# LED_BUFFER_v1.net
KiCad netlist of a schematic drawn in Altium Designer
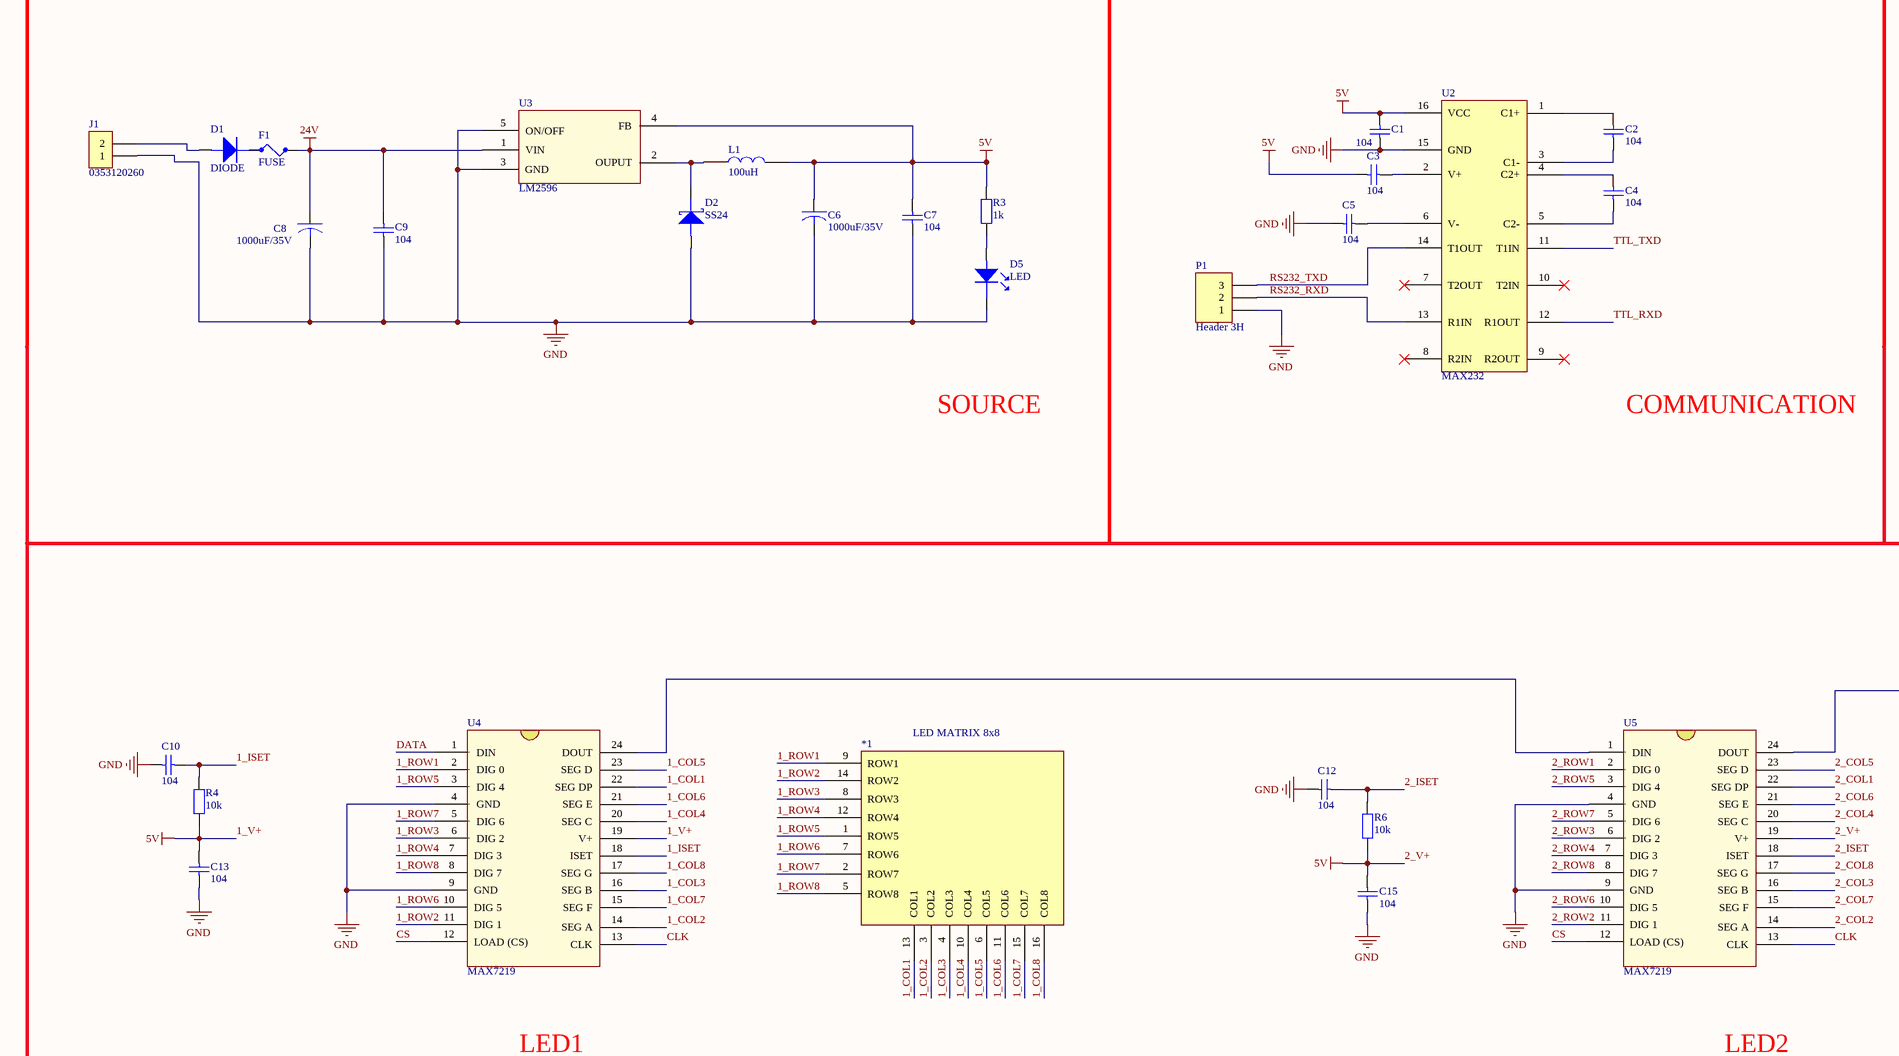
[diagram p0: LED_BUFFER_v1.SchDoc, top left]
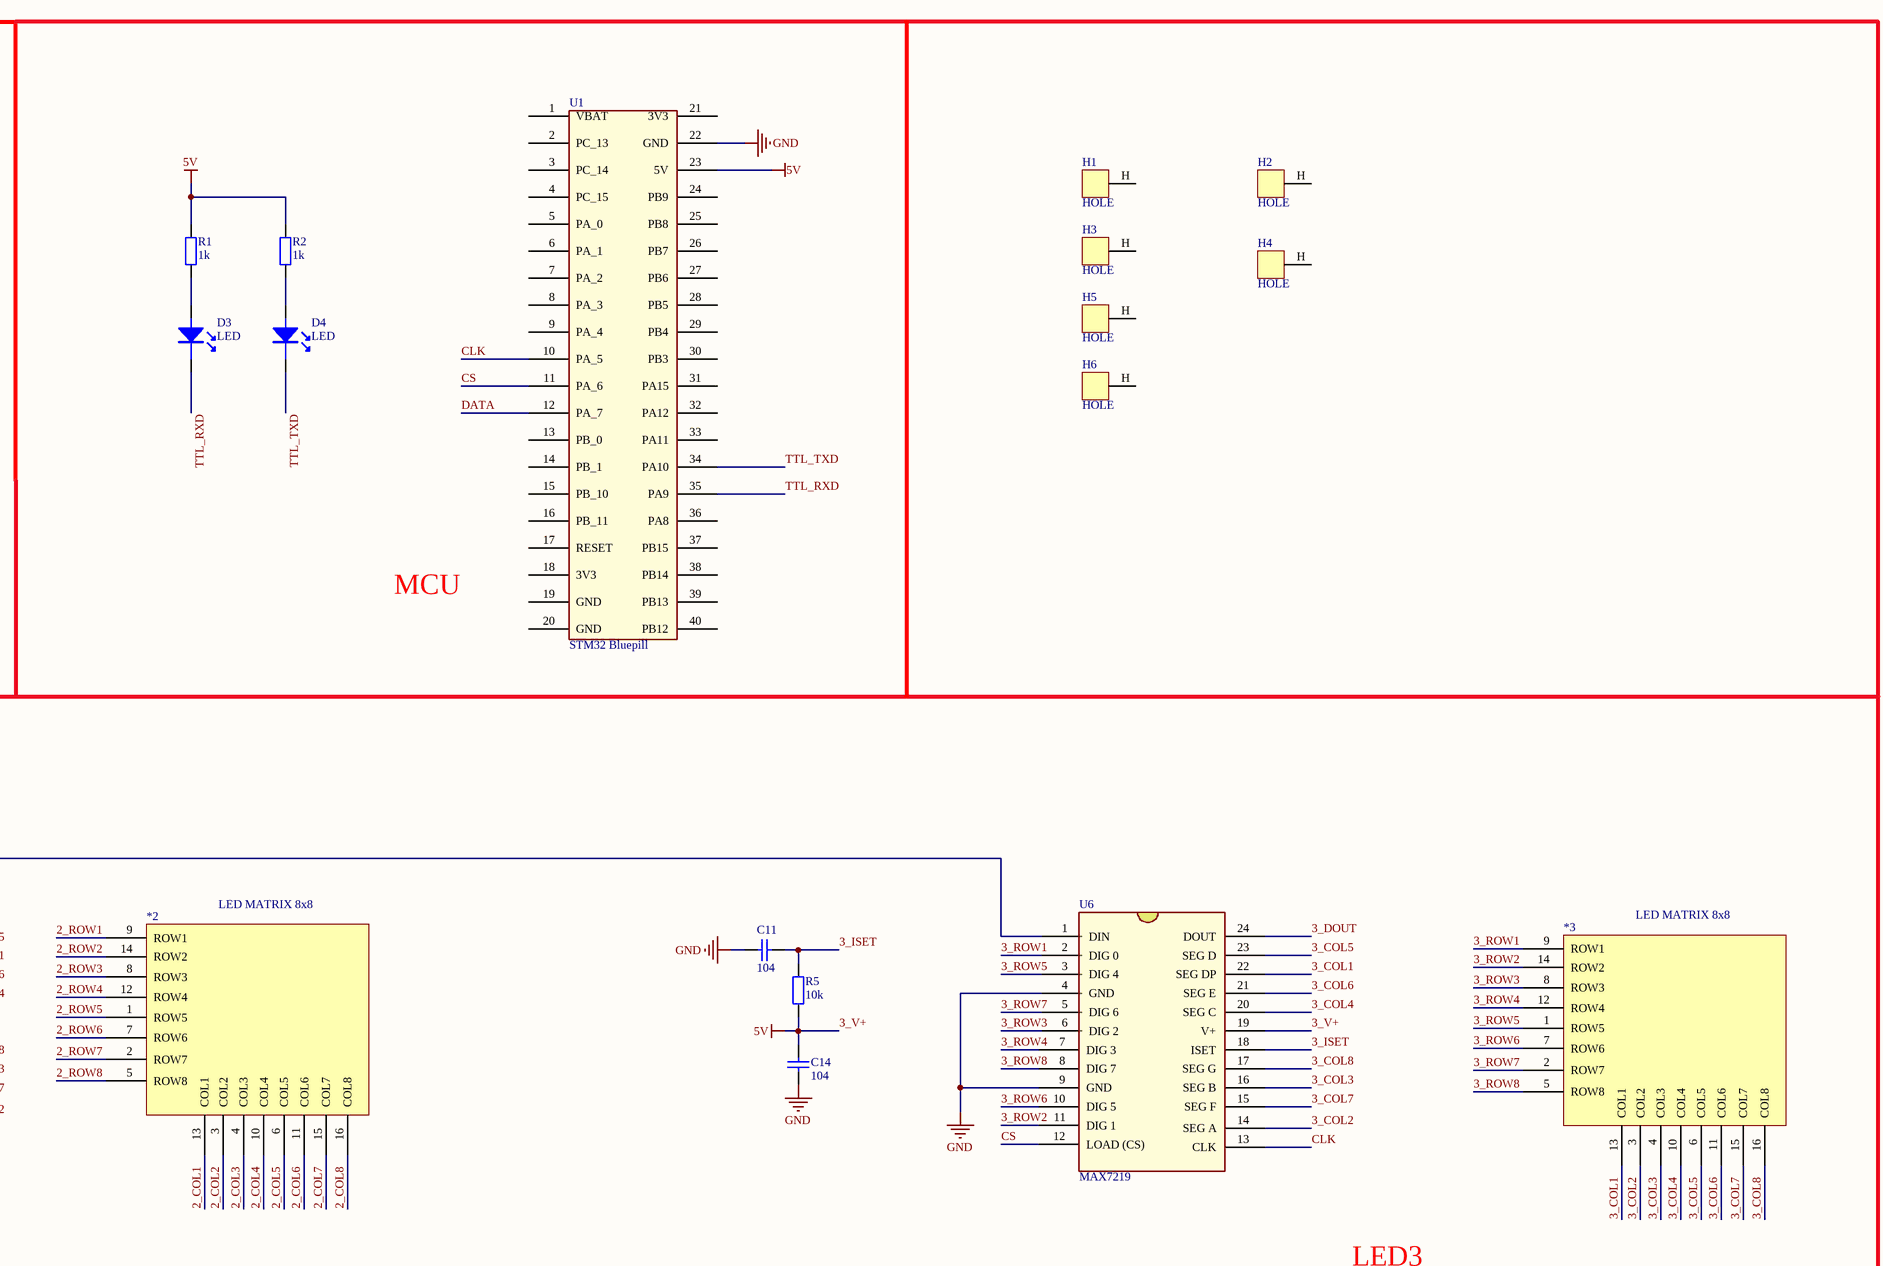
[diagram p1: LED_BUFFER_v1.SchDoc, top right]
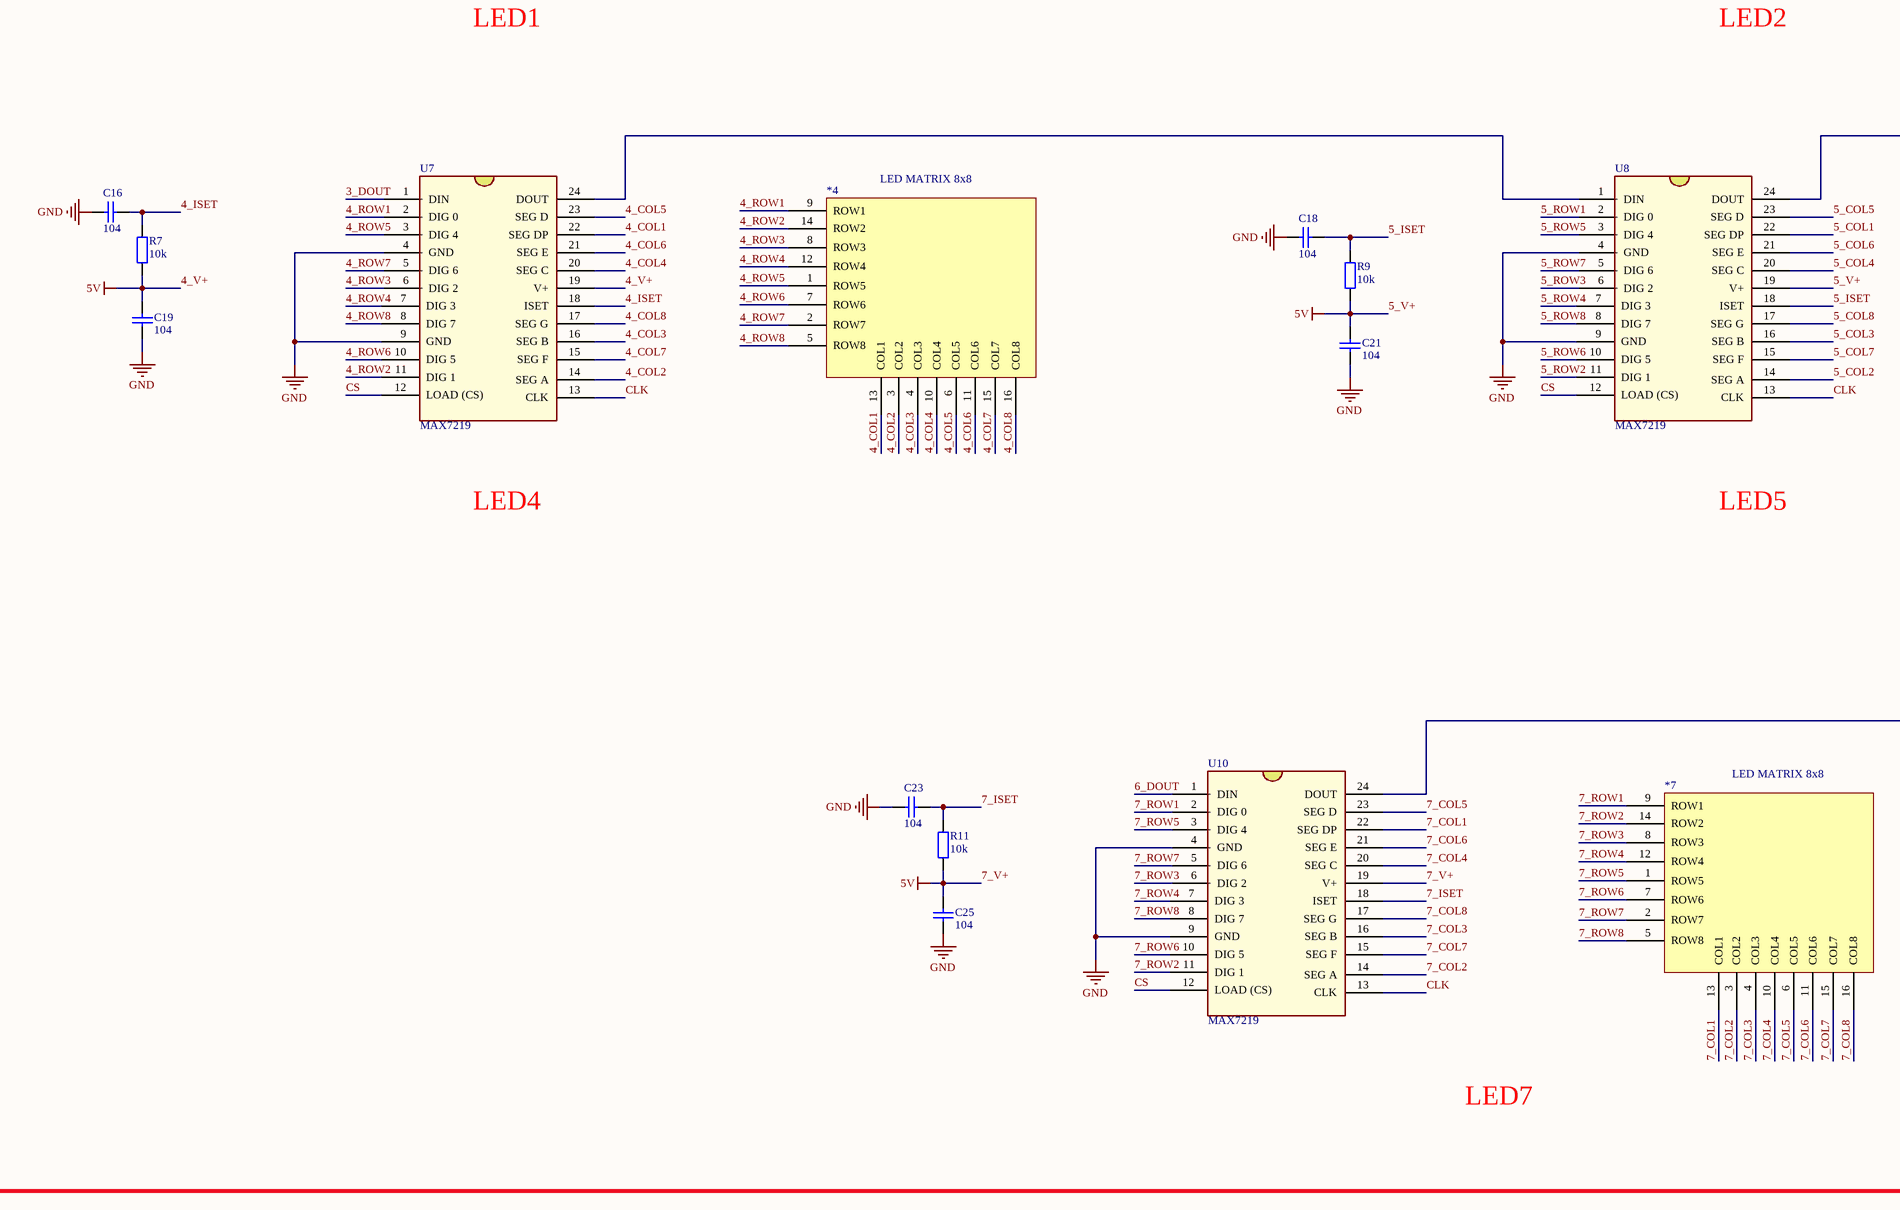
[diagram p2: LED_BUFFER_v1.SchDoc, bottom left]
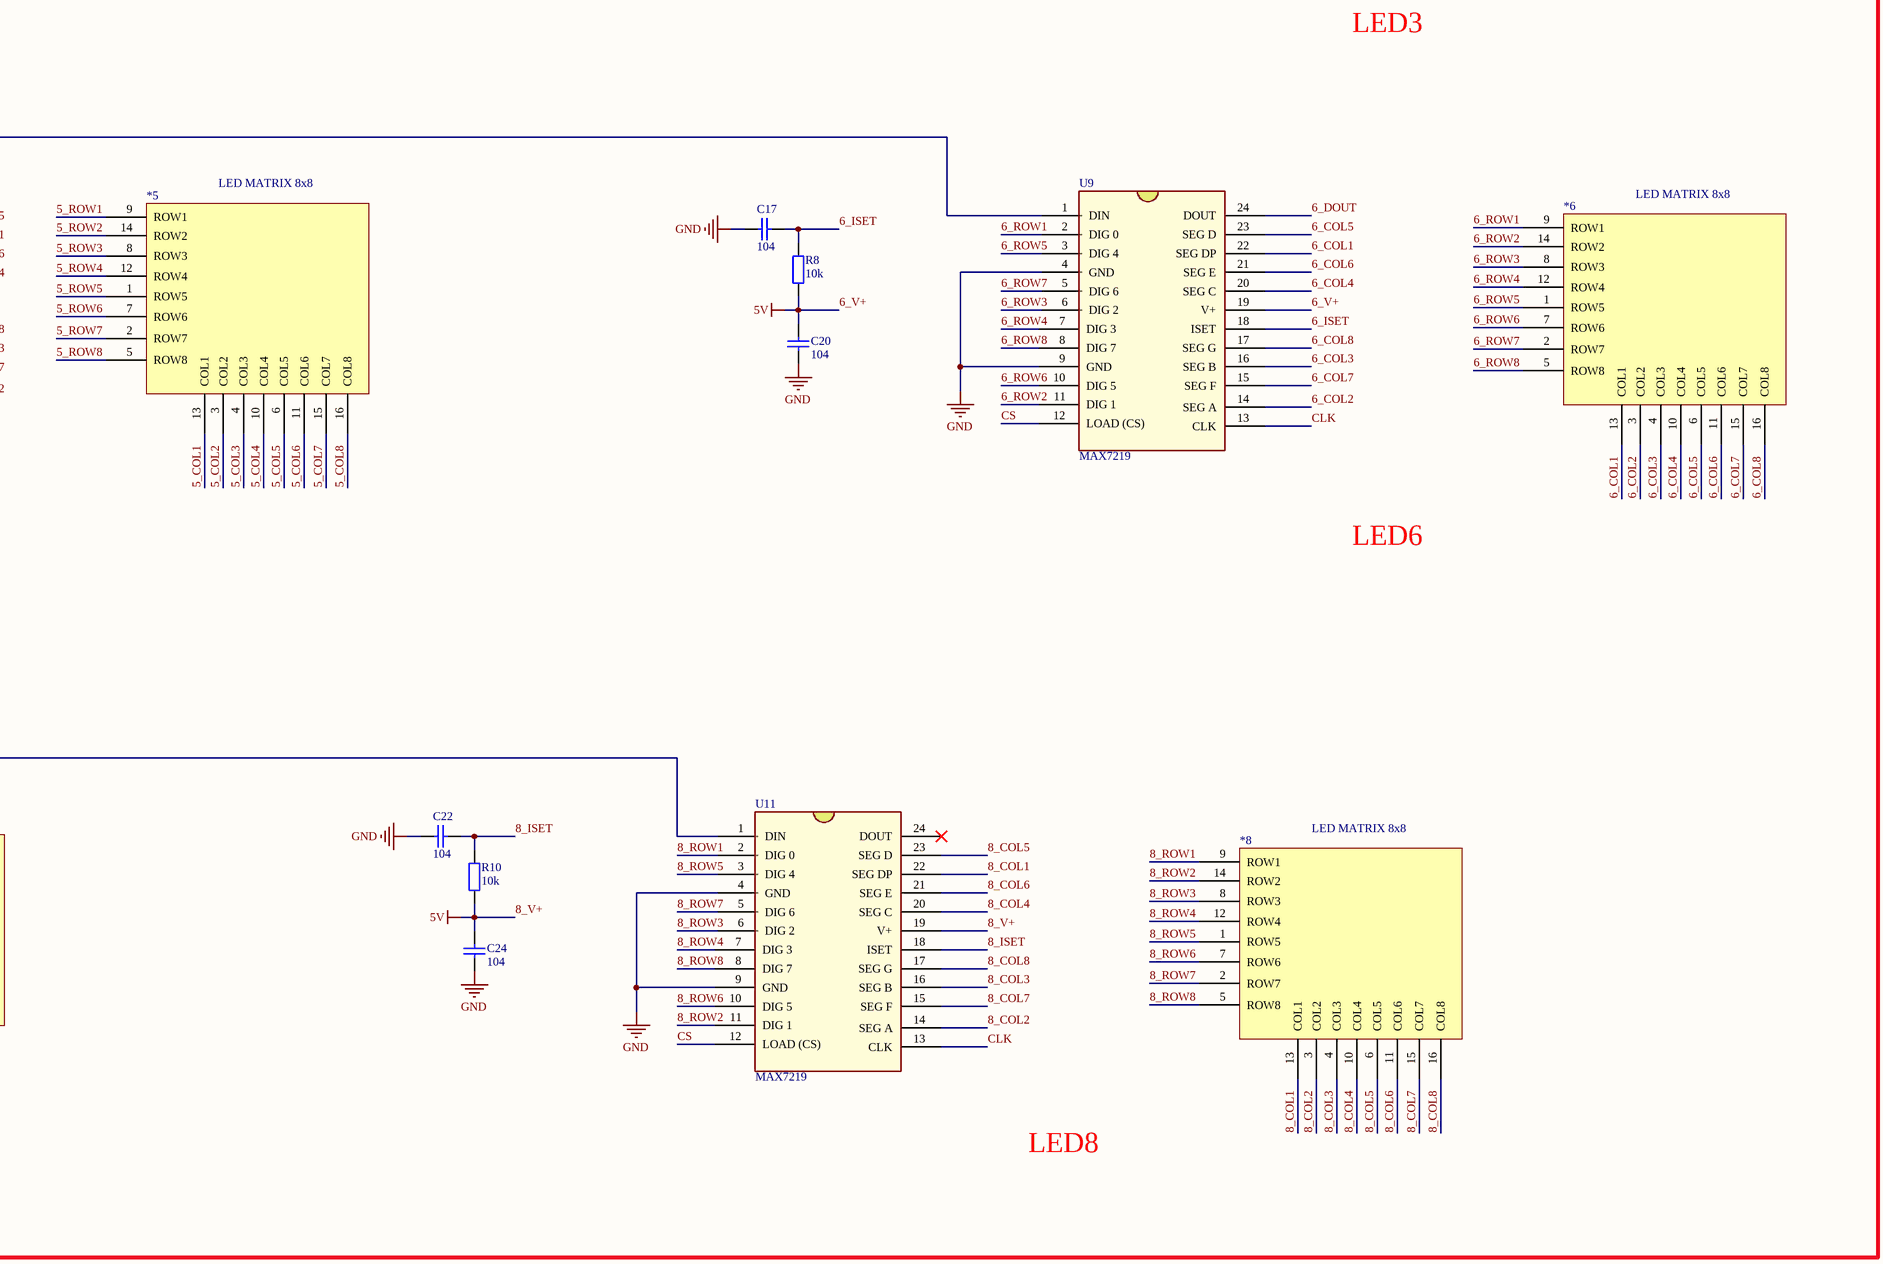
[diagram p3: LED_BUFFER_v1.SchDoc, bottom right]

(export (version "E")
  (design (tool "Eeschema 10.0.6"))
  (components
    (comp (ref "*1")
      (value "LED MATRIX 8x8")
      (footprint "LED MATRIX 8x8")
      (libsource (lib "VietHuy") (part "LED MATRIX 8x8"))
    )
    (comp (ref "*2")
      (value "LED MATRIX 8x8")
      (footprint "LED MATRIX 8x8")
      (libsource (lib "VietHuy") (part "LED MATRIX 8x8"))
    )
    (comp (ref "*3")
      (value "LED MATRIX 8x8")
      (footprint "LED MATRIX 8x8")
      (libsource (lib "VietHuy") (part "LED MATRIX 8x8"))
    )
    (comp (ref "*4")
      (value "LED MATRIX 8x8")
      (footprint "LED MATRIX 8x8")
      (libsource (lib "VietHuy") (part "LED MATRIX 8x8"))
    )
    (comp (ref "*5")
      (value "LED MATRIX 8x8")
      (footprint "LED MATRIX 8x8")
      (libsource (lib "VietHuy") (part "LED MATRIX 8x8"))
    )
    (comp (ref "*6")
      (value "LED MATRIX 8x8")
      (footprint "LED MATRIX 8x8")
      (libsource (lib "VietHuy") (part "LED MATRIX 8x8"))
    )
    (comp (ref "*7")
      (value "LED MATRIX 8x8")
      (footprint "LED MATRIX 8x8")
      (libsource (lib "VietHuy") (part "LED MATRIX 8x8"))
    )
    (comp (ref "*8")
      (value "LED MATRIX 8x8")
      (footprint "LED MATRIX 8x8")
      (libsource (lib "VietHuy") (part "LED MATRIX 8x8"))
    )
    (comp (ref "C1")
      (value "104")
      (footprint "0805 CAP")
      (fields (field (name "PUBLISHER") "Altium Limited"))
      (libsource (lib "ThinhNguyenLib") (part "CAP CERAMIC"))
    )
    (comp (ref "C2")
      (value "104")
      (footprint "0805 CAP")
      (fields (field (name "PUBLISHER") "Altium Limited"))
      (libsource (lib "ThinhNguyenLib") (part "CAP CERAMIC"))
    )
    (comp (ref "C3")
      (value "104")
      (footprint "0805 CAP")
      (fields (field (name "PUBLISHER") "Altium Limited"))
      (libsource (lib "ThinhNguyenLib") (part "CAP CERAMIC"))
    )
    (comp (ref "C4")
      (value "104")
      (footprint "0805 CAP")
      (fields (field (name "PUBLISHER") "Altium Limited"))
      (libsource (lib "ThinhNguyenLib") (part "CAP CERAMIC"))
    )
    (comp (ref "C5")
      (value "104")
      (footprint "0805 CAP")
      (fields (field (name "PUBLISHER") "Altium Limited"))
      (libsource (lib "ThinhNguyenLib") (part "CAP CERAMIC"))
    )
    (comp (ref "C6")
      (value "1000uF/35V")
      (footprint "CAP ALUMINUM SMD")
      (libsource (lib "ThinhNguyenLib") (part "CAPACITOR"))
    )
    (comp (ref "C7")
      (value "104")
      (footprint "0805 CAP")
      (fields (field (name "PUBLISHER") "Altium Limited"))
      (libsource (lib "ThinhNguyenLib") (part "CAP CERAMIC"))
    )
    (comp (ref "C8")
      (value "1000uF/35V")
      (footprint "CAP ALUMINUM SMD")
      (libsource (lib "ThinhNguyenLib") (part "CAPACITOR"))
    )
    (comp (ref "C9")
      (value "104")
      (footprint "0805 CAP")
      (fields (field (name "PUBLISHER") "Altium Limited"))
      (libsource (lib "ThinhNguyenLib") (part "CAP CERAMIC"))
    )
    (comp (ref "C10")
      (value "104")
      (footprint "0805 CAP")
      (fields (field (name "PUBLISHER") "Altium Limited"))
      (libsource (lib "ThinhNguyenLib") (part "CAP CERAMIC"))
    )
    (comp (ref "C11")
      (value "104")
      (footprint "0805 CAP")
      (fields (field (name "PUBLISHER") "Altium Limited"))
      (libsource (lib "ThinhNguyenLib") (part "CAP CERAMIC"))
    )
    (comp (ref "C12")
      (value "104")
      (footprint "0805 CAP")
      (fields (field (name "PUBLISHER") "Altium Limited"))
      (libsource (lib "ThinhNguyenLib") (part "CAP CERAMIC"))
    )
    (comp (ref "C13")
      (value "104")
      (footprint "0805 CAP")
      (fields (field (name "PUBLISHER") "Altium Limited"))
      (libsource (lib "ThinhNguyenLib") (part "CAP CERAMIC"))
    )
    (comp (ref "C14")
      (value "104")
      (footprint "0805 CAP")
      (fields (field (name "PUBLISHER") "Altium Limited"))
      (libsource (lib "ThinhNguyenLib") (part "CAP CERAMIC"))
    )
    (comp (ref "C15")
      (value "104")
      (footprint "0805 CAP")
      (fields (field (name "PUBLISHER") "Altium Limited"))
      (libsource (lib "ThinhNguyenLib") (part "CAP CERAMIC"))
    )
    (comp (ref "C16")
      (value "104")
      (footprint "0805 CAP")
      (fields (field (name "PUBLISHER") "Altium Limited"))
      (libsource (lib "ThinhNguyenLib") (part "CAP CERAMIC"))
    )
    (comp (ref "C17")
      (value "104")
      (footprint "0805 CAP")
      (fields (field (name "PUBLISHER") "Altium Limited"))
      (libsource (lib "ThinhNguyenLib") (part "CAP CERAMIC"))
    )
    (comp (ref "C18")
      (value "104")
      (footprint "0805 CAP")
      (fields (field (name "PUBLISHER") "Altium Limited"))
      (libsource (lib "ThinhNguyenLib") (part "CAP CERAMIC"))
    )
    (comp (ref "C19")
      (value "104")
      (footprint "0805 CAP")
      (fields (field (name "PUBLISHER") "Altium Limited"))
      (libsource (lib "ThinhNguyenLib") (part "CAP CERAMIC"))
    )
    (comp (ref "C20")
      (value "104")
      (footprint "0805 CAP")
      (fields (field (name "PUBLISHER") "Altium Limited"))
      (libsource (lib "ThinhNguyenLib") (part "CAP CERAMIC"))
    )
    (comp (ref "C21")
      (value "104")
      (footprint "0805 CAP")
      (fields (field (name "PUBLISHER") "Altium Limited"))
      (libsource (lib "ThinhNguyenLib") (part "CAP CERAMIC"))
    )
    (comp (ref "C22")
      (value "104")
      (footprint "0805 CAP")
      (fields (field (name "PUBLISHER") "Altium Limited"))
      (libsource (lib "ThinhNguyenLib") (part "CAP CERAMIC"))
    )
    (comp (ref "C23")
      (value "104")
      (footprint "0805 CAP")
      (fields (field (name "PUBLISHER") "Altium Limited"))
      (libsource (lib "ThinhNguyenLib") (part "CAP CERAMIC"))
    )
    (comp (ref "C24")
      (value "104")
      (footprint "0805 CAP")
      (fields (field (name "PUBLISHER") "Altium Limited"))
      (libsource (lib "ThinhNguyenLib") (part "CAP CERAMIC"))
    )
    (comp (ref "C25")
      (value "104")
      (footprint "0805 CAP")
      (fields (field (name "PUBLISHER") "Altium Limited"))
      (libsource (lib "ThinhNguyenLib") (part "CAP CERAMIC"))
    )
    (comp (ref "D1")
      (value "DIODE")
      (footprint "DIODE SMA")
      (libsource (lib "ThinhNguyenLib") (part "DIODE"))
    )
    (comp (ref "D2")
      (value "SS24")
      (footprint "DIODE ZENER SMD")
      (libsource (lib "ThinhNguyenLib") (part "SS1x"))
    )
    (comp (ref "D3") (value "LED") (footprint "LED SMD 0805") (libsource (lib "ThinhNguyenLib") (part "LED")))
    (comp (ref "D4") (value "LED") (footprint "LED SMD 0805") (libsource (lib "ThinhNguyenLib") (part "LED")))
    (comp (ref "D5") (value "LED") (footprint "LED SMD 0805") (libsource (lib "ThinhNguyenLib") (part "LED")))
    (comp (ref "F1")
      (value "FUSE")
      (footprint "FUSE 1812")
      (fields (field (name "ALTIUM_UNNAMED_1") "FUSE"))
      (libsource (lib "HHP_AGV_INTERFACES") (part "FUSE"))
    )
    (comp (ref "H1") (value "HOLE") (footprint "HOLE") (libsource (lib "ThinhNguyenLib") (part "HOLE")))
    (comp (ref "H2") (value "HOLE") (footprint "HOLE") (libsource (lib "ThinhNguyenLib") (part "HOLE")))
    (comp (ref "H3") (value "HOLE") (footprint "HOLE") (libsource (lib "ThinhNguyenLib") (part "HOLE")))
    (comp (ref "H4") (value "HOLE") (footprint "HOLE") (libsource (lib "ThinhNguyenLib") (part "HOLE")))
    (comp (ref "H5") (value "HOLE") (footprint "HOLE") (libsource (lib "ThinhNguyenLib") (part "HOLE")))
    (comp (ref "H6") (value "HOLE") (footprint "HOLE") (libsource (lib "ThinhNguyenLib") (part "HOLE")))
    (comp (ref "J1")
      (value "CONN HEADER VERT 2POS 2.5MM")
      (footprint "0353120260")
      (fields (field (name "P/N") "0353120260"))
      (libsource (lib "altium-import") (part "root_2_CONN HEADER VERT 2POS 2.5MM_"))
    )
    (comp (ref "L1")
      (value "100uH")
      (footprint "CDRH127 - 3A")
      (libsource (lib "ThinhNguyenLib") (part "INDUCTOR"))
    )
    (comp (ref "P1")
      (value "Header 3H")
      (footprint "HDR1X3 2mm")
      (fields (field (name "PUBLISHER") "Altium Limited"))
      (libsource (lib "ThinhNguyenLib") (part "Header 3H"))
    )
    (comp (ref "R1")
      (value "1k")
      (footprint "0805 RESISTOR")
      (libsource (lib "ThinhNguyenLib") (part "RESISTOR"))
    )
    (comp (ref "R2")
      (value "1k")
      (footprint "0805 RESISTOR")
      (libsource (lib "ThinhNguyenLib") (part "RESISTOR"))
    )
    (comp (ref "R3")
      (value "1k")
      (footprint "0805 RESISTOR")
      (libsource (lib "ThinhNguyenLib") (part "RESISTOR"))
    )
    (comp (ref "R4")
      (value "10k")
      (footprint "0805 RESISTOR")
      (libsource (lib "ThinhNguyenLib") (part "RESISTOR"))
    )
    (comp (ref "R5")
      (value "10k")
      (footprint "0805 RESISTOR")
      (libsource (lib "ThinhNguyenLib") (part "RESISTOR"))
    )
    (comp (ref "R6")
      (value "10k")
      (footprint "0805 RESISTOR")
      (libsource (lib "ThinhNguyenLib") (part "RESISTOR"))
    )
    (comp (ref "R7")
      (value "10k")
      (footprint "0805 RESISTOR")
      (libsource (lib "ThinhNguyenLib") (part "RESISTOR"))
    )
    (comp (ref "R8")
      (value "10k")
      (footprint "0805 RESISTOR")
      (libsource (lib "ThinhNguyenLib") (part "RESISTOR"))
    )
    (comp (ref "R9")
      (value "10k")
      (footprint "0805 RESISTOR")
      (libsource (lib "ThinhNguyenLib") (part "RESISTOR"))
    )
    (comp (ref "R10")
      (value "10k")
      (footprint "0805 RESISTOR")
      (libsource (lib "ThinhNguyenLib") (part "RESISTOR"))
    )
    (comp (ref "R11")
      (value "10k")
      (footprint "0805 RESISTOR")
      (libsource (lib "ThinhNguyenLib") (part "RESISTOR"))
    )
    (comp (ref "U1")
      (value "STM32 Bluepill")
      (footprint "Arduino STM32F103")
      (libsource (lib "VietHuy") (part "STM32 Bluepill"))
    )
    (comp (ref "U2") (value "MAX232") (footprint "SOIC 16PIN") (libsource (lib "VietHuy") (part "MAX232")))
    (comp (ref "U3") (value "LM2596") (footprint "TO263-5") (libsource (lib "VietHuy") (part "LM2596")))
    (comp (ref "U4")
      (value "MAX7219")
      (footprint "SOIC127P1030X265-24N")
      (libsource (lib "VietHuy") (part "MAX7219"))
    )
    (comp (ref "U5")
      (value "MAX7219")
      (footprint "SOIC127P1030X265-24N")
      (libsource (lib "VietHuy") (part "MAX7219"))
    )
    (comp (ref "U6")
      (value "MAX7219")
      (footprint "SOIC127P1030X265-24N")
      (libsource (lib "VietHuy") (part "MAX7219"))
    )
    (comp (ref "U7")
      (value "MAX7219")
      (footprint "SOIC127P1030X265-24N")
      (libsource (lib "VietHuy") (part "MAX7219"))
    )
    (comp (ref "U8")
      (value "MAX7219")
      (footprint "SOIC127P1030X265-24N")
      (libsource (lib "VietHuy") (part "MAX7219"))
    )
    (comp (ref "U9")
      (value "MAX7219")
      (footprint "SOIC127P1030X265-24N")
      (libsource (lib "VietHuy") (part "MAX7219"))
    )
    (comp (ref "U10")
      (value "MAX7219")
      (footprint "SOIC127P1030X265-24N")
      (libsource (lib "VietHuy") (part "MAX7219"))
    )
    (comp (ref "U11")
      (value "MAX7219")
      (footprint "SOIC127P1030X265-24N")
      (libsource (lib "VietHuy") (part "MAX7219"))
    )
  )
  (nets
    (net (code "1") (name "/1_COL1") (class "Default")
      (node (ref "*1") (pin "13") (pinfunction "COL1_13") (pintype "passive"))
      (node (ref "U4") (pin "22") (pinfunction "SEG_DP_22") (pintype "passive"))
    )
    (net (code "2") (name "/1_COL2") (class "Default")
      (node (ref "*1") (pin "3") (pinfunction "COL2_3") (pintype "passive"))
      (node (ref "U4") (pin "14") (pinfunction "SEG_A_14") (pintype "passive"))
    )
    (net (code "3") (name "/1_COL3") (class "Default")
      (node (ref "*1") (pin "4") (pinfunction "COL3_4") (pintype "passive"))
      (node (ref "U4") (pin "16") (pinfunction "SEG_B_16") (pintype "passive"))
    )
    (net (code "4") (name "/1_COL4") (class "Default")
      (node (ref "*1") (pin "10") (pinfunction "COL4_10") (pintype "passive"))
      (node (ref "U4") (pin "20") (pinfunction "SEG_C_20") (pintype "passive"))
    )
    (net (code "5") (name "/1_COL5") (class "Default")
      (node (ref "*1") (pin "6") (pinfunction "COL5_6") (pintype "passive"))
      (node (ref "U4") (pin "23") (pinfunction "SEG_D_23") (pintype "passive"))
    )
    (net (code "6") (name "/1_COL6") (class "Default")
      (node (ref "*1") (pin "11") (pinfunction "COL6_11") (pintype "passive"))
      (node (ref "U4") (pin "21") (pinfunction "SEG_E_21") (pintype "passive"))
    )
    (net (code "7") (name "/1_COL7") (class "Default")
      (node (ref "*1") (pin "15") (pinfunction "COL7_15") (pintype "passive"))
      (node (ref "U4") (pin "15") (pinfunction "SEG_F_15") (pintype "passive"))
    )
    (net (code "8") (name "/1_COL8") (class "Default")
      (node (ref "*1") (pin "16") (pinfunction "COL8_16") (pintype "passive"))
      (node (ref "U4") (pin "17") (pinfunction "SEG_G_17") (pintype "passive"))
    )
    (net (code "9") (name "/1_ISET") (class "Default")
      (node (ref "C10") (pin "2") (pinfunction "2_2") (pintype "passive"))
      (node (ref "R4") (pin "2") (pinfunction "2_2") (pintype "passive"))
      (node (ref "U4") (pin "18") (pinfunction "ISET_18") (pintype "passive"))
    )
    (net (code "10") (name "/1_ROW1") (class "Default")
      (node (ref "*1") (pin "9") (pinfunction "ROW1_9") (pintype "passive"))
      (node (ref "U4") (pin "2") (pinfunction "DIG_0_2") (pintype "passive"))
    )
    (net (code "11") (name "/1_ROW2") (class "Default")
      (node (ref "*1") (pin "14") (pinfunction "ROW2_14") (pintype "passive"))
      (node (ref "U4") (pin "11") (pinfunction "DIG_1_11") (pintype "passive"))
    )
    (net (code "12") (name "/1_ROW3") (class "Default")
      (node (ref "*1") (pin "8") (pinfunction "ROW3_8") (pintype "passive"))
      (node (ref "U4") (pin "6") (pinfunction "DIG_2_6") (pintype "passive"))
    )
    (net (code "13") (name "/1_ROW4") (class "Default")
      (node (ref "*1") (pin "12") (pinfunction "ROW4_12") (pintype "passive"))
      (node (ref "U4") (pin "7") (pinfunction "DIG_3_7") (pintype "passive"))
    )
    (net (code "14") (name "/1_ROW5") (class "Default")
      (node (ref "*1") (pin "1") (pinfunction "ROW5_1") (pintype "passive"))
      (node (ref "U4") (pin "3") (pinfunction "DIG_4_3") (pintype "passive"))
    )
    (net (code "15") (name "/1_ROW6") (class "Default")
      (node (ref "*1") (pin "7") (pinfunction "ROW6_7") (pintype "passive"))
      (node (ref "U4") (pin "10") (pinfunction "DIG_5_10") (pintype "passive"))
    )
    (net (code "16") (name "/1_ROW7") (class "Default")
      (node (ref "*1") (pin "2") (pinfunction "ROW7_2") (pintype "passive"))
      (node (ref "U4") (pin "5") (pinfunction "DIG_6_5") (pintype "passive"))
    )
    (net (code "17") (name "/1_ROW8") (class "Default")
      (node (ref "*1") (pin "5") (pinfunction "ROW8_5") (pintype "passive"))
      (node (ref "U4") (pin "8") (pinfunction "DIG_7_8") (pintype "passive"))
    )
    (net (code "18") (name "/2_COL1") (class "Default")
      (node (ref "*2") (pin "13") (pinfunction "COL1_13") (pintype "passive"))
      (node (ref "U5") (pin "22") (pinfunction "SEG_DP_22") (pintype "passive"))
    )
    (net (code "19") (name "/2_COL2") (class "Default")
      (node (ref "*2") (pin "3") (pinfunction "COL2_3") (pintype "passive"))
      (node (ref "U5") (pin "14") (pinfunction "SEG_A_14") (pintype "passive"))
    )
    (net (code "20") (name "/2_COL3") (class "Default")
      (node (ref "*2") (pin "4") (pinfunction "COL3_4") (pintype "passive"))
      (node (ref "U5") (pin "16") (pinfunction "SEG_B_16") (pintype "passive"))
    )
    (net (code "21") (name "/2_COL4") (class "Default")
      (node (ref "*2") (pin "10") (pinfunction "COL4_10") (pintype "passive"))
      (node (ref "U5") (pin "20") (pinfunction "SEG_C_20") (pintype "passive"))
    )
    (net (code "22") (name "/2_COL5") (class "Default")
      (node (ref "*2") (pin "6") (pinfunction "COL5_6") (pintype "passive"))
      (node (ref "U5") (pin "23") (pinfunction "SEG_D_23") (pintype "passive"))
    )
    (net (code "23") (name "/2_COL6") (class "Default")
      (node (ref "*2") (pin "11") (pinfunction "COL6_11") (pintype "passive"))
      (node (ref "U5") (pin "21") (pinfunction "SEG_E_21") (pintype "passive"))
    )
    (net (code "24") (name "/2_COL7") (class "Default")
      (node (ref "*2") (pin "15") (pinfunction "COL7_15") (pintype "passive"))
      (node (ref "U5") (pin "15") (pinfunction "SEG_F_15") (pintype "passive"))
    )
    (net (code "25") (name "/2_COL8") (class "Default")
      (node (ref "*2") (pin "16") (pinfunction "COL8_16") (pintype "passive"))
      (node (ref "U5") (pin "17") (pinfunction "SEG_G_17") (pintype "passive"))
    )
    (net (code "26") (name "/2_ISET") (class "Default")
      (node (ref "C12") (pin "2") (pinfunction "2_2") (pintype "passive"))
      (node (ref "R6") (pin "2") (pinfunction "2_2") (pintype "passive"))
      (node (ref "U5") (pin "18") (pinfunction "ISET_18") (pintype "passive"))
    )
    (net (code "27") (name "/2_ROW1") (class "Default")
      (node (ref "*2") (pin "9") (pinfunction "ROW1_9") (pintype "passive"))
      (node (ref "U5") (pin "2") (pinfunction "DIG_0_2") (pintype "passive"))
    )
    (net (code "28") (name "/2_ROW2") (class "Default")
      (node (ref "*2") (pin "14") (pinfunction "ROW2_14") (pintype "passive"))
      (node (ref "U5") (pin "11") (pinfunction "DIG_1_11") (pintype "passive"))
    )
    (net (code "29") (name "/2_ROW3") (class "Default")
      (node (ref "*2") (pin "8") (pinfunction "ROW3_8") (pintype "passive"))
      (node (ref "U5") (pin "6") (pinfunction "DIG_2_6") (pintype "passive"))
    )
    (net (code "30") (name "/2_ROW4") (class "Default")
      (node (ref "*2") (pin "12") (pinfunction "ROW4_12") (pintype "passive"))
      (node (ref "U5") (pin "7") (pinfunction "DIG_3_7") (pintype "passive"))
    )
    (net (code "31") (name "/2_ROW5") (class "Default")
      (node (ref "*2") (pin "1") (pinfunction "ROW5_1") (pintype "passive"))
      (node (ref "U5") (pin "3") (pinfunction "DIG_4_3") (pintype "passive"))
    )
    (net (code "32") (name "/2_ROW6") (class "Default")
      (node (ref "*2") (pin "7") (pinfunction "ROW6_7") (pintype "passive"))
      (node (ref "U5") (pin "10") (pinfunction "DIG_5_10") (pintype "passive"))
    )
    (net (code "33") (name "/2_ROW7") (class "Default")
      (node (ref "*2") (pin "2") (pinfunction "ROW7_2") (pintype "passive"))
      (node (ref "U5") (pin "5") (pinfunction "DIG_6_5") (pintype "passive"))
    )
    (net (code "34") (name "/2_ROW8") (class "Default")
      (node (ref "*2") (pin "5") (pinfunction "ROW8_5") (pintype "passive"))
      (node (ref "U5") (pin "8") (pinfunction "DIG_7_8") (pintype "passive"))
    )
    (net (code "35") (name "/3_COL1") (class "Default")
      (node (ref "*3") (pin "13") (pinfunction "COL1_13") (pintype "passive"))
      (node (ref "U6") (pin "22") (pinfunction "SEG_DP_22") (pintype "passive"))
    )
    (net (code "36") (name "/3_COL2") (class "Default")
      (node (ref "*3") (pin "3") (pinfunction "COL2_3") (pintype "passive"))
      (node (ref "U6") (pin "14") (pinfunction "SEG_A_14") (pintype "passive"))
    )
    (net (code "37") (name "/3_COL3") (class "Default")
      (node (ref "*3") (pin "4") (pinfunction "COL3_4") (pintype "passive"))
      (node (ref "U6") (pin "16") (pinfunction "SEG_B_16") (pintype "passive"))
    )
    (net (code "38") (name "/3_COL4") (class "Default")
      (node (ref "*3") (pin "10") (pinfunction "COL4_10") (pintype "passive"))
      (node (ref "U6") (pin "20") (pinfunction "SEG_C_20") (pintype "passive"))
    )
    (net (code "39") (name "/3_COL5") (class "Default")
      (node (ref "*3") (pin "6") (pinfunction "COL5_6") (pintype "passive"))
      (node (ref "U6") (pin "23") (pinfunction "SEG_D_23") (pintype "passive"))
    )
    (net (code "40") (name "/3_COL6") (class "Default")
      (node (ref "*3") (pin "11") (pinfunction "COL6_11") (pintype "passive"))
      (node (ref "U6") (pin "21") (pinfunction "SEG_E_21") (pintype "passive"))
    )
    (net (code "41") (name "/3_COL7") (class "Default")
      (node (ref "*3") (pin "15") (pinfunction "COL7_15") (pintype "passive"))
      (node (ref "U6") (pin "15") (pinfunction "SEG_F_15") (pintype "passive"))
    )
    (net (code "42") (name "/3_COL8") (class "Default")
      (node (ref "*3") (pin "16") (pinfunction "COL8_16") (pintype "passive"))
      (node (ref "U6") (pin "17") (pinfunction "SEG_G_17") (pintype "passive"))
    )
    (net (code "43") (name "/3_DOUT") (class "Default")
      (node (ref "U6") (pin "24") (pinfunction "DOUT_24") (pintype "passive"))
      (node (ref "U7") (pin "1") (pinfunction "DIN_1") (pintype "passive"))
    )
    (net (code "44") (name "/3_ISET") (class "Default")
      (node (ref "C11") (pin "2") (pinfunction "2_2") (pintype "passive"))
      (node (ref "R5") (pin "2") (pinfunction "2_2") (pintype "passive"))
      (node (ref "U6") (pin "18") (pinfunction "ISET_18") (pintype "passive"))
    )
    (net (code "45") (name "/3_ROW1") (class "Default")
      (node (ref "*3") (pin "9") (pinfunction "ROW1_9") (pintype "passive"))
      (node (ref "U6") (pin "2") (pinfunction "DIG_0_2") (pintype "passive"))
    )
    (net (code "46") (name "/3_ROW2") (class "Default")
      (node (ref "*3") (pin "14") (pinfunction "ROW2_14") (pintype "passive"))
      (node (ref "U6") (pin "11") (pinfunction "DIG_1_11") (pintype "passive"))
    )
    (net (code "47") (name "/3_ROW3") (class "Default")
      (node (ref "*3") (pin "8") (pinfunction "ROW3_8") (pintype "passive"))
      (node (ref "U6") (pin "6") (pinfunction "DIG_2_6") (pintype "passive"))
    )
    (net (code "48") (name "/3_ROW4") (class "Default")
      (node (ref "*3") (pin "12") (pinfunction "ROW4_12") (pintype "passive"))
      (node (ref "U6") (pin "7") (pinfunction "DIG_3_7") (pintype "passive"))
    )
    (net (code "49") (name "/3_ROW5") (class "Default")
      (node (ref "*3") (pin "1") (pinfunction "ROW5_1") (pintype "passive"))
      (node (ref "U6") (pin "3") (pinfunction "DIG_4_3") (pintype "passive"))
    )
    (net (code "50") (name "/3_ROW6") (class "Default")
      (node (ref "*3") (pin "7") (pinfunction "ROW6_7") (pintype "passive"))
      (node (ref "U6") (pin "10") (pinfunction "DIG_5_10") (pintype "passive"))
    )
    (net (code "51") (name "/3_ROW7") (class "Default")
      (node (ref "*3") (pin "2") (pinfunction "ROW7_2") (pintype "passive"))
      (node (ref "U6") (pin "5") (pinfunction "DIG_6_5") (pintype "passive"))
    )
    (net (code "52") (name "/3_ROW8") (class "Default")
      (node (ref "*3") (pin "5") (pinfunction "ROW8_5") (pintype "passive"))
      (node (ref "U6") (pin "8") (pinfunction "DIG_7_8") (pintype "passive"))
    )
    (net (code "53") (name "/4_COL1") (class "Default")
      (node (ref "*4") (pin "13") (pinfunction "COL1_13") (pintype "passive"))
      (node (ref "U7") (pin "22") (pinfunction "SEG_DP_22") (pintype "passive"))
    )
    (net (code "54") (name "/4_COL2") (class "Default")
      (node (ref "*4") (pin "3") (pinfunction "COL2_3") (pintype "passive"))
      (node (ref "U7") (pin "14") (pinfunction "SEG_A_14") (pintype "passive"))
    )
    (net (code "55") (name "/4_COL3") (class "Default")
      (node (ref "*4") (pin "4") (pinfunction "COL3_4") (pintype "passive"))
      (node (ref "U7") (pin "16") (pinfunction "SEG_B_16") (pintype "passive"))
    )
    (net (code "56") (name "/4_COL4") (class "Default")
      (node (ref "*4") (pin "10") (pinfunction "COL4_10") (pintype "passive"))
      (node (ref "U7") (pin "20") (pinfunction "SEG_C_20") (pintype "passive"))
    )
    (net (code "57") (name "/4_COL5") (class "Default")
      (node (ref "*4") (pin "6") (pinfunction "COL5_6") (pintype "passive"))
      (node (ref "U7") (pin "23") (pinfunction "SEG_D_23") (pintype "passive"))
    )
    (net (code "58") (name "/4_COL6") (class "Default")
      (node (ref "*4") (pin "11") (pinfunction "COL6_11") (pintype "passive"))
      (node (ref "U7") (pin "21") (pinfunction "SEG_E_21") (pintype "passive"))
    )
    (net (code "59") (name "/4_COL7") (class "Default")
      (node (ref "*4") (pin "15") (pinfunction "COL7_15") (pintype "passive"))
      (node (ref "U7") (pin "15") (pinfunction "SEG_F_15") (pintype "passive"))
    )
    (net (code "60") (name "/4_COL8") (class "Default")
      (node (ref "*4") (pin "16") (pinfunction "COL8_16") (pintype "passive"))
      (node (ref "U7") (pin "17") (pinfunction "SEG_G_17") (pintype "passive"))
    )
    (net (code "61") (name "/4_ISET") (class "Default")
      (node (ref "C16") (pin "2") (pinfunction "2_2") (pintype "passive"))
      (node (ref "R7") (pin "2") (pinfunction "2_2") (pintype "passive"))
      (node (ref "U7") (pin "18") (pinfunction "ISET_18") (pintype "passive"))
    )
    (net (code "62") (name "/4_ROW1") (class "Default")
      (node (ref "*4") (pin "9") (pinfunction "ROW1_9") (pintype "passive"))
      (node (ref "U7") (pin "2") (pinfunction "DIG_0_2") (pintype "passive"))
    )
    (net (code "63") (name "/4_ROW2") (class "Default")
      (node (ref "*4") (pin "14") (pinfunction "ROW2_14") (pintype "passive"))
      (node (ref "U7") (pin "11") (pinfunction "DIG_1_11") (pintype "passive"))
    )
    (net (code "64") (name "/4_ROW3") (class "Default")
      (node (ref "*4") (pin "8") (pinfunction "ROW3_8") (pintype "passive"))
      (node (ref "U7") (pin "6") (pinfunction "DIG_2_6") (pintype "passive"))
    )
    (net (code "65") (name "/4_ROW4") (class "Default")
      (node (ref "*4") (pin "12") (pinfunction "ROW4_12") (pintype "passive"))
      (node (ref "U7") (pin "7") (pinfunction "DIG_3_7") (pintype "passive"))
    )
    (net (code "66") (name "/4_ROW5") (class "Default")
      (node (ref "*4") (pin "1") (pinfunction "ROW5_1") (pintype "passive"))
      (node (ref "U7") (pin "3") (pinfunction "DIG_4_3") (pintype "passive"))
    )
    (net (code "67") (name "/4_ROW6") (class "Default")
      (node (ref "*4") (pin "7") (pinfunction "ROW6_7") (pintype "passive"))
      (node (ref "U7") (pin "10") (pinfunction "DIG_5_10") (pintype "passive"))
    )
    (net (code "68") (name "/4_ROW7") (class "Default")
      (node (ref "*4") (pin "2") (pinfunction "ROW7_2") (pintype "passive"))
      (node (ref "U7") (pin "5") (pinfunction "DIG_6_5") (pintype "passive"))
    )
    (net (code "69") (name "/4_ROW8") (class "Default")
      (node (ref "*4") (pin "5") (pinfunction "ROW8_5") (pintype "passive"))
      (node (ref "U7") (pin "8") (pinfunction "DIG_7_8") (pintype "passive"))
    )
    (net (code "70") (name "/5_COL1") (class "Default")
      (node (ref "*5") (pin "13") (pinfunction "COL1_13") (pintype "passive"))
      (node (ref "U8") (pin "22") (pinfunction "SEG_DP_22") (pintype "passive"))
    )
    (net (code "71") (name "/5_COL2") (class "Default")
      (node (ref "*5") (pin "3") (pinfunction "COL2_3") (pintype "passive"))
      (node (ref "U8") (pin "14") (pinfunction "SEG_A_14") (pintype "passive"))
    )
    (net (code "72") (name "/5_COL3") (class "Default")
      (node (ref "*5") (pin "4") (pinfunction "COL3_4") (pintype "passive"))
      (node (ref "U8") (pin "16") (pinfunction "SEG_B_16") (pintype "passive"))
    )
    (net (code "73") (name "/5_COL4") (class "Default")
      (node (ref "*5") (pin "10") (pinfunction "COL4_10") (pintype "passive"))
      (node (ref "U8") (pin "20") (pinfunction "SEG_C_20") (pintype "passive"))
    )
    (net (code "74") (name "/5_COL5") (class "Default")
      (node (ref "*5") (pin "6") (pinfunction "COL5_6") (pintype "passive"))
      (node (ref "U8") (pin "23") (pinfunction "SEG_D_23") (pintype "passive"))
    )
    (net (code "75") (name "/5_COL6") (class "Default")
      (node (ref "*5") (pin "11") (pinfunction "COL6_11") (pintype "passive"))
      (node (ref "U8") (pin "21") (pinfunction "SEG_E_21") (pintype "passive"))
    )
    (net (code "76") (name "/5_COL7") (class "Default")
      (node (ref "*5") (pin "15") (pinfunction "COL7_15") (pintype "passive"))
      (node (ref "U8") (pin "15") (pinfunction "SEG_F_15") (pintype "passive"))
    )
    (net (code "77") (name "/5_COL8") (class "Default")
      (node (ref "*5") (pin "16") (pinfunction "COL8_16") (pintype "passive"))
      (node (ref "U8") (pin "17") (pinfunction "SEG_G_17") (pintype "passive"))
    )
    (net (code "78") (name "/5_ISET") (class "Default")
      (node (ref "C18") (pin "2") (pinfunction "2_2") (pintype "passive"))
      (node (ref "R9") (pin "2") (pinfunction "2_2") (pintype "passive"))
      (node (ref "U8") (pin "18") (pinfunction "ISET_18") (pintype "passive"))
    )
    (net (code "79") (name "/5_ROW1") (class "Default")
      (node (ref "*5") (pin "9") (pinfunction "ROW1_9") (pintype "passive"))
      (node (ref "U8") (pin "2") (pinfunction "DIG_0_2") (pintype "passive"))
    )
    (net (code "80") (name "/5_ROW2") (class "Default")
      (node (ref "*5") (pin "14") (pinfunction "ROW2_14") (pintype "passive"))
      (node (ref "U8") (pin "11") (pinfunction "DIG_1_11") (pintype "passive"))
    )
    (net (code "81") (name "/5_ROW3") (class "Default")
      (node (ref "*5") (pin "8") (pinfunction "ROW3_8") (pintype "passive"))
      (node (ref "U8") (pin "6") (pinfunction "DIG_2_6") (pintype "passive"))
    )
    (net (code "82") (name "/5_ROW4") (class "Default")
      (node (ref "*5") (pin "12") (pinfunction "ROW4_12") (pintype "passive"))
      (node (ref "U8") (pin "7") (pinfunction "DIG_3_7") (pintype "passive"))
    )
    (net (code "83") (name "/5_ROW5") (class "Default")
      (node (ref "*5") (pin "1") (pinfunction "ROW5_1") (pintype "passive"))
      (node (ref "U8") (pin "3") (pinfunction "DIG_4_3") (pintype "passive"))
    )
    (net (code "84") (name "/5_ROW6") (class "Default")
      (node (ref "*5") (pin "7") (pinfunction "ROW6_7") (pintype "passive"))
      (node (ref "U8") (pin "10") (pinfunction "DIG_5_10") (pintype "passive"))
    )
    (net (code "85") (name "/5_ROW7") (class "Default")
      (node (ref "*5") (pin "2") (pinfunction "ROW7_2") (pintype "passive"))
      (node (ref "U8") (pin "5") (pinfunction "DIG_6_5") (pintype "passive"))
    )
    (net (code "86") (name "/5_ROW8") (class "Default")
      (node (ref "*5") (pin "5") (pinfunction "ROW8_5") (pintype "passive"))
      (node (ref "U8") (pin "8") (pinfunction "DIG_7_8") (pintype "passive"))
    )
    (net (code "87") (name "/6_COL1") (class "Default")
      (node (ref "*6") (pin "13") (pinfunction "COL1_13") (pintype "passive"))
      (node (ref "U9") (pin "22") (pinfunction "SEG_DP_22") (pintype "passive"))
    )
    (net (code "88") (name "/6_COL2") (class "Default")
      (node (ref "*6") (pin "3") (pinfunction "COL2_3") (pintype "passive"))
      (node (ref "U9") (pin "14") (pinfunction "SEG_A_14") (pintype "passive"))
    )
    (net (code "89") (name "/6_COL3") (class "Default")
      (node (ref "*6") (pin "4") (pinfunction "COL3_4") (pintype "passive"))
      (node (ref "U9") (pin "16") (pinfunction "SEG_B_16") (pintype "passive"))
    )
    (net (code "90") (name "/6_COL4") (class "Default")
      (node (ref "*6") (pin "10") (pinfunction "COL4_10") (pintype "passive"))
      (node (ref "U9") (pin "20") (pinfunction "SEG_C_20") (pintype "passive"))
    )
    (net (code "91") (name "/6_COL5") (class "Default")
      (node (ref "*6") (pin "6") (pinfunction "COL5_6") (pintype "passive"))
      (node (ref "U9") (pin "23") (pinfunction "SEG_D_23") (pintype "passive"))
    )
    (net (code "92") (name "/6_COL6") (class "Default")
      (node (ref "*6") (pin "11") (pinfunction "COL6_11") (pintype "passive"))
      (node (ref "U9") (pin "21") (pinfunction "SEG_E_21") (pintype "passive"))
    )
    (net (code "93") (name "/6_COL7") (class "Default")
      (node (ref "*6") (pin "15") (pinfunction "COL7_15") (pintype "passive"))
      (node (ref "U9") (pin "15") (pinfunction "SEG_F_15") (pintype "passive"))
    )
    (net (code "94") (name "/6_COL8") (class "Default")
      (node (ref "*6") (pin "16") (pinfunction "COL8_16") (pintype "passive"))
      (node (ref "U9") (pin "17") (pinfunction "SEG_G_17") (pintype "passive"))
    )
    (net (code "95") (name "/6_DOUT") (class "Default")
      (node (ref "U10") (pin "1") (pinfunction "DIN_1") (pintype "passive"))
      (node (ref "U9") (pin "24") (pinfunction "DOUT_24") (pintype "passive"))
    )
    (net (code "96") (name "/6_ISET") (class "Default")
      (node (ref "C17") (pin "2") (pinfunction "2_2") (pintype "passive"))
      (node (ref "R8") (pin "2") (pinfunction "2_2") (pintype "passive"))
      (node (ref "U9") (pin "18") (pinfunction "ISET_18") (pintype "passive"))
    )
    (net (code "97") (name "/6_ROW1") (class "Default")
      (node (ref "*6") (pin "9") (pinfunction "ROW1_9") (pintype "passive"))
      (node (ref "U9") (pin "2") (pinfunction "DIG_0_2") (pintype "passive"))
    )
    (net (code "98") (name "/6_ROW2") (class "Default")
      (node (ref "*6") (pin "14") (pinfunction "ROW2_14") (pintype "passive"))
      (node (ref "U9") (pin "11") (pinfunction "DIG_1_11") (pintype "passive"))
    )
    (net (code "99") (name "/6_ROW3") (class "Default")
      (node (ref "*6") (pin "8") (pinfunction "ROW3_8") (pintype "passive"))
      (node (ref "U9") (pin "6") (pinfunction "DIG_2_6") (pintype "passive"))
    )
    (net (code "100") (name "/6_ROW4") (class "Default")
      (node (ref "*6") (pin "12") (pinfunction "ROW4_12") (pintype "passive"))
      (node (ref "U9") (pin "7") (pinfunction "DIG_3_7") (pintype "passive"))
    )
    (net (code "101") (name "/6_ROW5") (class "Default")
      (node (ref "*6") (pin "1") (pinfunction "ROW5_1") (pintype "passive"))
      (node (ref "U9") (pin "3") (pinfunction "DIG_4_3") (pintype "passive"))
    )
    (net (code "102") (name "/6_ROW6") (class "Default")
      (node (ref "*6") (pin "7") (pinfunction "ROW6_7") (pintype "passive"))
      (node (ref "U9") (pin "10") (pinfunction "DIG_5_10") (pintype "passive"))
    )
    (net (code "103") (name "/6_ROW7") (class "Default")
      (node (ref "*6") (pin "2") (pinfunction "ROW7_2") (pintype "passive"))
      (node (ref "U9") (pin "5") (pinfunction "DIG_6_5") (pintype "passive"))
    )
    (net (code "104") (name "/6_ROW8") (class "Default")
      (node (ref "*6") (pin "5") (pinfunction "ROW8_5") (pintype "passive"))
      (node (ref "U9") (pin "8") (pinfunction "DIG_7_8") (pintype "passive"))
    )
    (net (code "105") (name "/7_COL1") (class "Default")
      (node (ref "*7") (pin "13") (pinfunction "COL1_13") (pintype "passive"))
      (node (ref "U10") (pin "22") (pinfunction "SEG_DP_22") (pintype "passive"))
    )
    (net (code "106") (name "/7_COL2") (class "Default")
      (node (ref "*7") (pin "3") (pinfunction "COL2_3") (pintype "passive"))
      (node (ref "U10") (pin "14") (pinfunction "SEG_A_14") (pintype "passive"))
    )
    (net (code "107") (name "/7_COL3") (class "Default")
      (node (ref "*7") (pin "4") (pinfunction "COL3_4") (pintype "passive"))
      (node (ref "U10") (pin "16") (pinfunction "SEG_B_16") (pintype "passive"))
    )
    (net (code "108") (name "/7_COL4") (class "Default")
      (node (ref "*7") (pin "10") (pinfunction "COL4_10") (pintype "passive"))
      (node (ref "U10") (pin "20") (pinfunction "SEG_C_20") (pintype "passive"))
    )
    (net (code "109") (name "/7_COL5") (class "Default")
      (node (ref "*7") (pin "6") (pinfunction "COL5_6") (pintype "passive"))
      (node (ref "U10") (pin "23") (pinfunction "SEG_D_23") (pintype "passive"))
    )
    (net (code "110") (name "/7_COL6") (class "Default")
      (node (ref "*7") (pin "11") (pinfunction "COL6_11") (pintype "passive"))
      (node (ref "U10") (pin "21") (pinfunction "SEG_E_21") (pintype "passive"))
    )
    (net (code "111") (name "/7_COL7") (class "Default")
      (node (ref "*7") (pin "15") (pinfunction "COL7_15") (pintype "passive"))
      (node (ref "U10") (pin "15") (pinfunction "SEG_F_15") (pintype "passive"))
    )
    (net (code "112") (name "/7_COL8") (class "Default")
      (node (ref "*7") (pin "16") (pinfunction "COL8_16") (pintype "passive"))
      (node (ref "U10") (pin "17") (pinfunction "SEG_G_17") (pintype "passive"))
    )
    (net (code "113") (name "/7_ISET") (class "Default")
      (node (ref "C23") (pin "2") (pinfunction "2_2") (pintype "passive"))
      (node (ref "R11") (pin "2") (pinfunction "2_2") (pintype "passive"))
      (node (ref "U10") (pin "18") (pinfunction "ISET_18") (pintype "passive"))
    )
    (net (code "114") (name "/7_ROW1") (class "Default")
      (node (ref "*7") (pin "9") (pinfunction "ROW1_9") (pintype "passive"))
      (node (ref "U10") (pin "2") (pinfunction "DIG_0_2") (pintype "passive"))
    )
    (net (code "115") (name "/7_ROW2") (class "Default")
      (node (ref "*7") (pin "14") (pinfunction "ROW2_14") (pintype "passive"))
      (node (ref "U10") (pin "11") (pinfunction "DIG_1_11") (pintype "passive"))
    )
    (net (code "116") (name "/7_ROW3") (class "Default")
      (node (ref "*7") (pin "8") (pinfunction "ROW3_8") (pintype "passive"))
      (node (ref "U10") (pin "6") (pinfunction "DIG_2_6") (pintype "passive"))
    )
    (net (code "117") (name "/7_ROW4") (class "Default")
      (node (ref "*7") (pin "12") (pinfunction "ROW4_12") (pintype "passive"))
      (node (ref "U10") (pin "7") (pinfunction "DIG_3_7") (pintype "passive"))
    )
    (net (code "118") (name "/7_ROW5") (class "Default")
      (node (ref "*7") (pin "1") (pinfunction "ROW5_1") (pintype "passive"))
      (node (ref "U10") (pin "3") (pinfunction "DIG_4_3") (pintype "passive"))
    )
    (net (code "119") (name "/7_ROW6") (class "Default")
      (node (ref "*7") (pin "7") (pinfunction "ROW6_7") (pintype "passive"))
      (node (ref "U10") (pin "10") (pinfunction "DIG_5_10") (pintype "passive"))
    )
    (net (code "120") (name "/7_ROW7") (class "Default")
      (node (ref "*7") (pin "2") (pinfunction "ROW7_2") (pintype "passive"))
      (node (ref "U10") (pin "5") (pinfunction "DIG_6_5") (pintype "passive"))
    )
    (net (code "121") (name "/7_ROW8") (class "Default")
      (node (ref "*7") (pin "5") (pinfunction "ROW8_5") (pintype "passive"))
      (node (ref "U10") (pin "8") (pinfunction "DIG_7_8") (pintype "passive"))
    )
    (net (code "122") (name "/8_COL1") (class "Default")
      (node (ref "*8") (pin "13") (pinfunction "COL1_13") (pintype "passive"))
      (node (ref "U11") (pin "22") (pinfunction "SEG_DP_22") (pintype "passive"))
    )
    (net (code "123") (name "/8_COL2") (class "Default")
      (node (ref "*8") (pin "3") (pinfunction "COL2_3") (pintype "passive"))
      (node (ref "U11") (pin "14") (pinfunction "SEG_A_14") (pintype "passive"))
    )
    (net (code "124") (name "/8_COL3") (class "Default")
      (node (ref "*8") (pin "4") (pinfunction "COL3_4") (pintype "passive"))
      (node (ref "U11") (pin "16") (pinfunction "SEG_B_16") (pintype "passive"))
    )
    (net (code "125") (name "/8_COL4") (class "Default")
      (node (ref "*8") (pin "10") (pinfunction "COL4_10") (pintype "passive"))
      (node (ref "U11") (pin "20") (pinfunction "SEG_C_20") (pintype "passive"))
    )
    (net (code "126") (name "/8_COL5") (class "Default")
      (node (ref "*8") (pin "6") (pinfunction "COL5_6") (pintype "passive"))
      (node (ref "U11") (pin "23") (pinfunction "SEG_D_23") (pintype "passive"))
    )
    (net (code "127") (name "/8_COL6") (class "Default")
      (node (ref "*8") (pin "11") (pinfunction "COL6_11") (pintype "passive"))
      (node (ref "U11") (pin "21") (pinfunction "SEG_E_21") (pintype "passive"))
    )
    (net (code "128") (name "/8_COL7") (class "Default")
      (node (ref "*8") (pin "15") (pinfunction "COL7_15") (pintype "passive"))
      (node (ref "U11") (pin "15") (pinfunction "SEG_F_15") (pintype "passive"))
    )
    (net (code "129") (name "/8_COL8") (class "Default")
      (node (ref "*8") (pin "16") (pinfunction "COL8_16") (pintype "passive"))
      (node (ref "U11") (pin "17") (pinfunction "SEG_G_17") (pintype "passive"))
    )
    (net (code "130") (name "/8_ISET") (class "Default")
      (node (ref "C22") (pin "2") (pinfunction "2_2") (pintype "passive"))
      (node (ref "R10") (pin "2") (pinfunction "2_2") (pintype "passive"))
      (node (ref "U11") (pin "18") (pinfunction "ISET_18") (pintype "passive"))
    )
    (net (code "131") (name "/8_ROW1") (class "Default")
      (node (ref "*8") (pin "9") (pinfunction "ROW1_9") (pintype "passive"))
      (node (ref "U11") (pin "2") (pinfunction "DIG_0_2") (pintype "passive"))
    )
    (net (code "132") (name "/8_ROW2") (class "Default")
      (node (ref "*8") (pin "14") (pinfunction "ROW2_14") (pintype "passive"))
      (node (ref "U11") (pin "11") (pinfunction "DIG_1_11") (pintype "passive"))
    )
    (net (code "133") (name "/8_ROW3") (class "Default")
      (node (ref "*8") (pin "8") (pinfunction "ROW3_8") (pintype "passive"))
      (node (ref "U11") (pin "6") (pinfunction "DIG_2_6") (pintype "passive"))
    )
    (net (code "134") (name "/8_ROW4") (class "Default")
      (node (ref "*8") (pin "12") (pinfunction "ROW4_12") (pintype "passive"))
      (node (ref "U11") (pin "7") (pinfunction "DIG_3_7") (pintype "passive"))
    )
    (net (code "135") (name "/8_ROW5") (class "Default")
      (node (ref "*8") (pin "1") (pinfunction "ROW5_1") (pintype "passive"))
      (node (ref "U11") (pin "3") (pinfunction "DIG_4_3") (pintype "passive"))
    )
    (net (code "136") (name "/8_ROW6") (class "Default")
      (node (ref "*8") (pin "7") (pinfunction "ROW6_7") (pintype "passive"))
      (node (ref "U11") (pin "10") (pinfunction "DIG_5_10") (pintype "passive"))
    )
    (net (code "137") (name "/8_ROW7") (class "Default")
      (node (ref "*8") (pin "2") (pinfunction "ROW7_2") (pintype "passive"))
      (node (ref "U11") (pin "5") (pinfunction "DIG_6_5") (pintype "passive"))
    )
    (net (code "138") (name "/8_ROW8") (class "Default")
      (node (ref "*8") (pin "5") (pinfunction "ROW8_5") (pintype "passive"))
      (node (ref "U11") (pin "8") (pinfunction "DIG_7_8") (pintype "passive"))
    )
    (net (code "139") (name "/CLK") (class "Default")
      (node (ref "U1") (pin "10") (pinfunction "PA_5_10") (pintype "passive"))
      (node (ref "U10") (pin "13") (pinfunction "CLK_13") (pintype "passive"))
      (node (ref "U11") (pin "13") (pinfunction "CLK_13") (pintype "passive"))
      (node (ref "U4") (pin "13") (pinfunction "CLK_13") (pintype "passive"))
      (node (ref "U5") (pin "13") (pinfunction "CLK_13") (pintype "passive"))
      (node (ref "U6") (pin "13") (pinfunction "CLK_13") (pintype "passive"))
      (node (ref "U7") (pin "13") (pinfunction "CLK_13") (pintype "passive"))
      (node (ref "U8") (pin "13") (pinfunction "CLK_13") (pintype "passive"))
      (node (ref "U9") (pin "13") (pinfunction "CLK_13") (pintype "passive"))
    )
    (net (code "140") (name "/CS") (class "Default")
      (node (ref "U1") (pin "11") (pinfunction "PA_6_11") (pintype "passive"))
      (node (ref "U10") (pin "12") (pinfunction "LOAD_(CS)_12") (pintype "passive"))
      (node (ref "U11") (pin "12") (pinfunction "LOAD_(CS)_12") (pintype "passive"))
      (node (ref "U4") (pin "12") (pinfunction "LOAD_(CS)_12") (pintype "passive"))
      (node (ref "U5") (pin "12") (pinfunction "LOAD_(CS)_12") (pintype "passive"))
      (node (ref "U6") (pin "12") (pinfunction "LOAD_(CS)_12") (pintype "passive"))
      (node (ref "U7") (pin "12") (pinfunction "LOAD_(CS)_12") (pintype "passive"))
      (node (ref "U8") (pin "12") (pinfunction "LOAD_(CS)_12") (pintype "passive"))
      (node (ref "U9") (pin "12") (pinfunction "LOAD_(CS)_12") (pintype "passive"))
    )
    (net (code "141") (name "/DATA") (class "Default")
      (node (ref "U1") (pin "12") (pinfunction "PA_7_12") (pintype "passive"))
      (node (ref "U4") (pin "1") (pinfunction "DIN_1") (pintype "passive"))
    )
    (net (code "142") (name "/RS232_RXD") (class "Default")
      (node (ref "P1") (pin "2") (pinfunction "2_2") (pintype "passive"))
      (node (ref "U2") (pin "13") (pinfunction "R1IN_13") (pintype "passive"))
    )
    (net (code "143") (name "/RS232_TXD") (class "Default")
      (node (ref "P1") (pin "3") (pinfunction "3_3") (pintype "passive"))
      (node (ref "U2") (pin "14") (pinfunction "T1OUT_14") (pintype "passive"))
    )
    (net (code "144") (name "/TTL_RXD") (class "Default")
      (node (ref "D3") (pin "2") (pinfunction "2_2") (pintype "passive"))
      (node (ref "U1") (pin "35") (pinfunction "PA9_35") (pintype "passive"))
      (node (ref "U2") (pin "12") (pinfunction "R1OUT_12") (pintype "passive"))
    )
    (net (code "145") (name "/TTL_TXD") (class "Default")
      (node (ref "D4") (pin "2") (pinfunction "2_2") (pintype "passive"))
      (node (ref "U1") (pin "34") (pinfunction "PA10_34") (pintype "passive"))
      (node (ref "U2") (pin "11") (pinfunction "T1IN_11") (pintype "passive"))
    )
    (net (code "146") (name "5V") (class "Default")
      (node (ref "C1") (pin "2") (pinfunction "2_2") (pintype "passive"))
      (node (ref "C13") (pin "1") (pinfunction "1_1") (pintype "passive"))
      (node (ref "C14") (pin "1") (pinfunction "1_1") (pintype "passive"))
      (node (ref "C15") (pin "1") (pinfunction "1_1") (pintype "passive"))
      (node (ref "C19") (pin "1") (pinfunction "1_1") (pintype "passive"))
      (node (ref "C20") (pin "1") (pinfunction "1_1") (pintype "passive"))
      (node (ref "C21") (pin "1") (pinfunction "1_1") (pintype "passive"))
      (node (ref "C24") (pin "1") (pinfunction "1_1") (pintype "passive"))
      (node (ref "C25") (pin "1") (pinfunction "1_1") (pintype "passive"))
      (node (ref "C3") (pin "1") (pinfunction "1_1") (pintype "passive"))
      (node (ref "C6") (pin "1") (pinfunction "1_1") (pintype "passive"))
      (node (ref "C7") (pin "1") (pinfunction "1_1") (pintype "passive"))
      (node (ref "L1") (pin "2") (pinfunction "2_2") (pintype "passive"))
      (node (ref "R1") (pin "2") (pinfunction "2_2") (pintype "passive"))
      (node (ref "R10") (pin "1") (pinfunction "1_1") (pintype "passive"))
      (node (ref "R11") (pin "1") (pinfunction "1_1") (pintype "passive"))
      (node (ref "R2") (pin "2") (pinfunction "2_2") (pintype "passive"))
      (node (ref "R3") (pin "2") (pinfunction "2_2") (pintype "passive"))
      (node (ref "R4") (pin "1") (pinfunction "1_1") (pintype "passive"))
      (node (ref "R5") (pin "1") (pinfunction "1_1") (pintype "passive"))
      (node (ref "R6") (pin "1") (pinfunction "1_1") (pintype "passive"))
      (node (ref "R7") (pin "1") (pinfunction "1_1") (pintype "passive"))
      (node (ref "R8") (pin "1") (pinfunction "1_1") (pintype "passive"))
      (node (ref "R9") (pin "1") (pinfunction "1_1") (pintype "passive"))
      (node (ref "U1") (pin "23") (pinfunction "5V_23") (pintype "passive"))
      (node (ref "U10") (pin "19") (pinfunction "V+_19") (pintype "passive"))
      (node (ref "U11") (pin "19") (pinfunction "V+_19") (pintype "passive"))
      (node (ref "U2") (pin "16") (pinfunction "VCC_16") (pintype "passive"))
      (node (ref "U3") (pin "4") (pinfunction "FB_4") (pintype "passive"))
      (node (ref "U4") (pin "19") (pinfunction "V+_19") (pintype "passive"))
      (node (ref "U5") (pin "19") (pinfunction "V+_19") (pintype "passive"))
      (node (ref "U6") (pin "19") (pinfunction "V+_19") (pintype "passive"))
      (node (ref "U7") (pin "19") (pinfunction "V+_19") (pintype "passive"))
      (node (ref "U8") (pin "19") (pinfunction "V+_19") (pintype "passive"))
      (node (ref "U9") (pin "19") (pinfunction "V+_19") (pintype "passive"))
    )
    (net (code "147") (name "24V") (class "Default")
      (node (ref "C8") (pin "1") (pinfunction "1_1") (pintype "passive"))
      (node (ref "C9") (pin "1") (pinfunction "1_1") (pintype "passive"))
      (node (ref "F1") (pin "1") (pinfunction "1_1") (pintype "passive"))
      (node (ref "U3") (pin "1") (pinfunction "VIN_1") (pintype "passive"))
    )
    (net (code "148") (name "GND") (class "Default")
      (node (ref "C1") (pin "1") (pinfunction "1_1") (pintype "passive"))
      (node (ref "C10") (pin "1") (pinfunction "1_1") (pintype "passive"))
      (node (ref "C11") (pin "1") (pinfunction "1_1") (pintype "passive"))
      (node (ref "C12") (pin "1") (pinfunction "1_1") (pintype "passive"))
      (node (ref "C13") (pin "2") (pinfunction "2_2") (pintype "passive"))
      (node (ref "C14") (pin "2") (pinfunction "2_2") (pintype "passive"))
      (node (ref "C15") (pin "2") (pinfunction "2_2") (pintype "passive"))
      (node (ref "C16") (pin "1") (pinfunction "1_1") (pintype "passive"))
      (node (ref "C17") (pin "1") (pinfunction "1_1") (pintype "passive"))
      (node (ref "C18") (pin "1") (pinfunction "1_1") (pintype "passive"))
      (node (ref "C19") (pin "2") (pinfunction "2_2") (pintype "passive"))
      (node (ref "C20") (pin "2") (pinfunction "2_2") (pintype "passive"))
      (node (ref "C21") (pin "2") (pinfunction "2_2") (pintype "passive"))
      (node (ref "C22") (pin "1") (pinfunction "1_1") (pintype "passive"))
      (node (ref "C23") (pin "1") (pinfunction "1_1") (pintype "passive"))
      (node (ref "C24") (pin "2") (pinfunction "2_2") (pintype "passive"))
      (node (ref "C25") (pin "2") (pinfunction "2_2") (pintype "passive"))
      (node (ref "C5") (pin "1") (pinfunction "1_1") (pintype "passive"))
      (node (ref "C6") (pin "2") (pinfunction "2_2") (pintype "passive"))
      (node (ref "C7") (pin "2") (pinfunction "2_2") (pintype "passive"))
      (node (ref "C8") (pin "2") (pinfunction "2_2") (pintype "passive"))
      (node (ref "C9") (pin "2") (pinfunction "2_2") (pintype "passive"))
      (node (ref "D2") (pin "1") (pinfunction "A_1") (pintype "passive"))
      (node (ref "D5") (pin "2") (pinfunction "2_2") (pintype "passive"))
      (node (ref "J1") (pin "1") (pinfunction "1_1") (pintype "passive"))
      (node (ref "P1") (pin "1") (pinfunction "1_1") (pintype "passive"))
      (node (ref "U1") (pin "22") (pinfunction "GND_22") (pintype "passive"))
      (node (ref "U10") (pin "4") (pinfunction "GND_4") (pintype "passive"))
      (node (ref "U10") (pin "9") (pinfunction "GND_9") (pintype "passive"))
      (node (ref "U11") (pin "4") (pinfunction "GND_4") (pintype "passive"))
      (node (ref "U11") (pin "9") (pinfunction "GND_9") (pintype "passive"))
      (node (ref "U2") (pin "15") (pinfunction "GND_15") (pintype "passive"))
      (node (ref "U3") (pin "3") (pinfunction "GND_3") (pintype "passive"))
      (node (ref "U3") (pin "5") (pinfunction "ON/OFF_5") (pintype "passive"))
      (node (ref "U4") (pin "4") (pinfunction "GND_4") (pintype "passive"))
      (node (ref "U4") (pin "9") (pinfunction "GND_9") (pintype "passive"))
      (node (ref "U5") (pin "4") (pinfunction "GND_4") (pintype "passive"))
      (node (ref "U5") (pin "9") (pinfunction "GND_9") (pintype "passive"))
      (node (ref "U6") (pin "4") (pinfunction "GND_4") (pintype "passive"))
      (node (ref "U6") (pin "9") (pinfunction "GND_9") (pintype "passive"))
      (node (ref "U7") (pin "4") (pinfunction "GND_4") (pintype "passive"))
      (node (ref "U7") (pin "9") (pinfunction "GND_9") (pintype "passive"))
      (node (ref "U8") (pin "4") (pinfunction "GND_4") (pintype "passive"))
      (node (ref "U8") (pin "9") (pinfunction "GND_9") (pintype "passive"))
      (node (ref "U9") (pin "4") (pinfunction "GND_4") (pintype "passive"))
      (node (ref "U9") (pin "9") (pinfunction "GND_9") (pintype "passive"))
    )
    (net (code "149") (name "Net-(D1-Pad1)") (class "Default")
      (node (ref "D1") (pin "1") (pinfunction "1_1") (pintype "passive"))
      (node (ref "J1") (pin "2") (pinfunction "2_2") (pintype "passive"))
    )
    (net (code "150") (name "Net-(D1-Pad2)") (class "Default")
      (node (ref "D1") (pin "2") (pinfunction "2_2") (pintype "passive"))
      (node (ref "F1") (pin "2") (pinfunction "2_2") (pintype "passive"))
    )
    (net (code "151") (name "Net-(D2-K)") (class "Default")
      (node (ref "D2") (pin "2") (pinfunction "K_2") (pintype "passive"))
      (node (ref "L1") (pin "1") (pinfunction "1_1") (pintype "passive"))
      (node (ref "U3") (pin "2") (pinfunction "OUPUT_2") (pintype "passive"))
    )
    (net (code "152") (name "Net-(D3-Pad1)") (class "Default")
      (node (ref "D3") (pin "1") (pinfunction "1_1") (pintype "passive"))
      (node (ref "R1") (pin "1") (pinfunction "1_1") (pintype "passive"))
    )
    (net (code "153") (name "Net-(D4-Pad1)") (class "Default")
      (node (ref "D4") (pin "1") (pinfunction "1_1") (pintype "passive"))
      (node (ref "R2") (pin "1") (pinfunction "1_1") (pintype "passive"))
    )
    (net (code "154") (name "Net-(D5-Pad1)") (class "Default")
      (node (ref "D5") (pin "1") (pinfunction "1_1") (pintype "passive"))
      (node (ref "R3") (pin "1") (pinfunction "1_1") (pintype "passive"))
    )
    (net (code "155") (name "Net-(U2-C1+)") (class "Default")
      (node (ref "C2") (pin "2") (pinfunction "2_2") (pintype "passive"))
      (node (ref "U2") (pin "1") (pinfunction "C1+_1") (pintype "passive"))
    )
    (net (code "156") (name "Net-(U2-C1-)") (class "Default")
      (node (ref "C2") (pin "1") (pinfunction "1_1") (pintype "passive"))
      (node (ref "U2") (pin "3") (pinfunction "C1-_3") (pintype "passive"))
    )
    (net (code "157") (name "Net-(U2-C2+)") (class "Default")
      (node (ref "C4") (pin "1") (pinfunction "1_1") (pintype "passive"))
      (node (ref "U2") (pin "4") (pinfunction "C2+_4") (pintype "passive"))
    )
    (net (code "158") (name "Net-(U2-C2-)") (class "Default")
      (node (ref "C4") (pin "2") (pinfunction "2_2") (pintype "passive"))
      (node (ref "U2") (pin "5") (pinfunction "C2-_5") (pintype "passive"))
    )
    (net (code "159") (name "Net-(U2-V+)") (class "Default")
      (node (ref "C3") (pin "2") (pinfunction "2_2") (pintype "passive"))
      (node (ref "U2") (pin "2") (pinfunction "V+_2") (pintype "passive"))
    )
    (net (code "160") (name "Net-(U2-V-)") (class "Default")
      (node (ref "C5") (pin "2") (pinfunction "2_2") (pintype "passive"))
      (node (ref "U2") (pin "6") (pinfunction "V-_6") (pintype "passive"))
    )
    (net (code "161") (name "Net-(U4-DOUT)") (class "Default")
      (node (ref "U4") (pin "24") (pinfunction "DOUT_24") (pintype "passive"))
      (node (ref "U5") (pin "1") (pinfunction "DIN_1") (pintype "passive"))
    )
    (net (code "162") (name "Net-(U5-DOUT)") (class "Default")
      (node (ref "U5") (pin "24") (pinfunction "DOUT_24") (pintype "passive"))
      (node (ref "U6") (pin "1") (pinfunction "DIN_1") (pintype "passive"))
    )
    (net (code "163") (name "Net-(U7-DOUT)") (class "Default")
      (node (ref "U7") (pin "24") (pinfunction "DOUT_24") (pintype "passive"))
      (node (ref "U8") (pin "1") (pinfunction "DIN_1") (pintype "passive"))
    )
    (net (code "164") (name "Net-(U8-DOUT)") (class "Default")
      (node (ref "U8") (pin "24") (pinfunction "DOUT_24") (pintype "passive"))
      (node (ref "U9") (pin "1") (pinfunction "DIN_1") (pintype "passive"))
    )
    (net (code "165") (name "Net-(U10-DOUT)") (class "Default")
      (node (ref "U10") (pin "24") (pinfunction "DOUT_24") (pintype "passive"))
      (node (ref "U11") (pin "1") (pinfunction "DIN_1") (pintype "passive"))
    )
    (net (code "166") (name "unconnected-(H1-HOLE-PadH)") (class "Default")
      (node (ref "H1") (pin "H") (pinfunction "HOLE_H") (pintype "passive"))
    )
    (net (code "167") (name "unconnected-(H2-HOLE-PadH)") (class "Default")
      (node (ref "H2") (pin "H") (pinfunction "HOLE_H") (pintype "passive"))
    )
    (net (code "168") (name "unconnected-(H3-HOLE-PadH)") (class "Default")
      (node (ref "H3") (pin "H") (pinfunction "HOLE_H") (pintype "passive"))
    )
    (net (code "169") (name "unconnected-(H4-HOLE-PadH)") (class "Default")
      (node (ref "H4") (pin "H") (pinfunction "HOLE_H") (pintype "passive"))
    )
    (net (code "170") (name "unconnected-(H5-HOLE-PadH)") (class "Default")
      (node (ref "H5") (pin "H") (pinfunction "HOLE_H") (pintype "passive"))
    )
    (net (code "171") (name "unconnected-(H6-HOLE-PadH)") (class "Default")
      (node (ref "H6") (pin "H") (pinfunction "HOLE_H") (pintype "passive"))
    )
    (net (code "172") (name "unconnected-(U1-3V3-Pad18)") (class "Default")
      (node (ref "U1") (pin "18") (pinfunction "3V3_18") (pintype "passive"))
    )
    (net (code "173") (name "unconnected-(U1-3V3-Pad21)") (class "Default")
      (node (ref "U1") (pin "21") (pinfunction "3V3_21") (pintype "passive"))
    )
    (net (code "174") (name "unconnected-(U1-GND-Pad19)") (class "Default")
      (node (ref "U1") (pin "19") (pinfunction "GND_19") (pintype "passive"))
    )
    (net (code "175") (name "unconnected-(U1-GND-Pad20)") (class "Default")
      (node (ref "U1") (pin "20") (pinfunction "GND_20") (pintype "passive"))
    )
    (net (code "176") (name "unconnected-(U1-PA8-Pad36)") (class "Default")
      (node (ref "U1") (pin "36") (pinfunction "PA8_36") (pintype "passive"))
    )
    (net (code "177") (name "unconnected-(U1-PA11-Pad33)") (class "Default")
      (node (ref "U1") (pin "33") (pinfunction "PA11_33") (pintype "passive"))
    )
    (net (code "178") (name "unconnected-(U1-PA12-Pad32)") (class "Default")
      (node (ref "U1") (pin "32") (pinfunction "PA12_32") (pintype "passive"))
    )
    (net (code "179") (name "unconnected-(U1-PA15-Pad31)") (class "Default")
      (node (ref "U1") (pin "31") (pinfunction "PA15_31") (pintype "passive"))
    )
    (net (code "180") (name "unconnected-(U1-PA_0-Pad5)") (class "Default")
      (node (ref "U1") (pin "5") (pinfunction "PA_0_5") (pintype "passive"))
    )
    (net (code "181") (name "unconnected-(U1-PA_1-Pad6)") (class "Default")
      (node (ref "U1") (pin "6") (pinfunction "PA_1_6") (pintype "passive"))
    )
    (net (code "182") (name "unconnected-(U1-PA_2-Pad7)") (class "Default")
      (node (ref "U1") (pin "7") (pinfunction "PA_2_7") (pintype "passive"))
    )
    (net (code "183") (name "unconnected-(U1-PA_3-Pad8)") (class "Default")
      (node (ref "U1") (pin "8") (pinfunction "PA_3_8") (pintype "passive"))
    )
    (net (code "184") (name "unconnected-(U1-PA_4-Pad9)") (class "Default")
      (node (ref "U1") (pin "9") (pinfunction "PA_4_9") (pintype "passive"))
    )
    (net (code "185") (name "unconnected-(U1-PB3-Pad30)") (class "Default")
      (node (ref "U1") (pin "30") (pinfunction "PB3_30") (pintype "passive"))
    )
    (net (code "186") (name "unconnected-(U1-PB4-Pad29)") (class "Default")
      (node (ref "U1") (pin "29") (pinfunction "PB4_29") (pintype "passive"))
    )
    (net (code "187") (name "unconnected-(U1-PB5-Pad28)") (class "Default")
      (node (ref "U1") (pin "28") (pinfunction "PB5_28") (pintype "passive"))
    )
    (net (code "188") (name "unconnected-(U1-PB6-Pad27)") (class "Default")
      (node (ref "U1") (pin "27") (pinfunction "PB6_27") (pintype "passive"))
    )
    (net (code "189") (name "unconnected-(U1-PB7-Pad26)") (class "Default")
      (node (ref "U1") (pin "26") (pinfunction "PB7_26") (pintype "passive"))
    )
    (net (code "190") (name "unconnected-(U1-PB8-Pad25)") (class "Default")
      (node (ref "U1") (pin "25") (pinfunction "PB8_25") (pintype "passive"))
    )
    (net (code "191") (name "unconnected-(U1-PB9-Pad24)") (class "Default")
      (node (ref "U1") (pin "24") (pinfunction "PB9_24") (pintype "passive"))
    )
    (net (code "192") (name "unconnected-(U1-PB12-Pad40)") (class "Default")
      (node (ref "U1") (pin "40") (pinfunction "PB12_40") (pintype "passive"))
    )
    (net (code "193") (name "unconnected-(U1-PB13-Pad39)") (class "Default")
      (node (ref "U1") (pin "39") (pinfunction "PB13_39") (pintype "passive"))
    )
    (net (code "194") (name "unconnected-(U1-PB14-Pad38)") (class "Default")
      (node (ref "U1") (pin "38") (pinfunction "PB14_38") (pintype "passive"))
    )
    (net (code "195") (name "unconnected-(U1-PB15-Pad37)") (class "Default")
      (node (ref "U1") (pin "37") (pinfunction "PB15_37") (pintype "passive"))
    )
    (net (code "196") (name "unconnected-(U1-PB_0-Pad13)") (class "Default")
      (node (ref "U1") (pin "13") (pinfunction "PB_0_13") (pintype "passive"))
    )
    (net (code "197") (name "unconnected-(U1-PB_1-Pad14)") (class "Default")
      (node (ref "U1") (pin "14") (pinfunction "PB_1_14") (pintype "passive"))
    )
    (net (code "198") (name "unconnected-(U1-PB_10-Pad15)") (class "Default")
      (node (ref "U1") (pin "15") (pinfunction "PB_10_15") (pintype "passive"))
    )
    (net (code "199") (name "unconnected-(U1-PB_11-Pad16)") (class "Default")
      (node (ref "U1") (pin "16") (pinfunction "PB_11_16") (pintype "passive"))
    )
    (net (code "200") (name "unconnected-(U1-PC_13-Pad2)") (class "Default")
      (node (ref "U1") (pin "2") (pinfunction "PC_13_2") (pintype "passive"))
    )
    (net (code "201") (name "unconnected-(U1-PC_14-Pad3)") (class "Default")
      (node (ref "U1") (pin "3") (pinfunction "PC_14_3") (pintype "passive"))
    )
    (net (code "202") (name "unconnected-(U1-PC_15-Pad4)") (class "Default")
      (node (ref "U1") (pin "4") (pinfunction "PC_15_4") (pintype "passive"))
    )
    (net (code "203") (name "unconnected-(U1-RESET-Pad17)") (class "Default")
      (node (ref "U1") (pin "17") (pinfunction "RESET_17") (pintype "passive"))
    )
    (net (code "204") (name "unconnected-(U1-VBAT-Pad1)") (class "Default")
      (node (ref "U1") (pin "1") (pinfunction "VBAT_1") (pintype "passive"))
    )
    (net (code "205") (name "unconnected-(U2-R2IN-Pad8)") (class "Default")
      (node (ref "U2") (pin "8") (pinfunction "R2IN_8") (pintype "passive+no_connect"))
    )
    (net (code "206") (name "unconnected-(U2-R2OUT-Pad9)") (class "Default")
      (node (ref "U2") (pin "9") (pinfunction "R2OUT_9") (pintype "passive+no_connect"))
    )
    (net (code "207") (name "unconnected-(U2-T2IN-Pad10)") (class "Default")
      (node (ref "U2") (pin "10") (pinfunction "T2IN_10") (pintype "passive+no_connect"))
    )
    (net (code "208") (name "unconnected-(U2-T2OUT-Pad7)") (class "Default")
      (node (ref "U2") (pin "7") (pinfunction "T2OUT_7") (pintype "passive+no_connect"))
    )
    (net (code "209") (name "unconnected-(U11-DOUT-Pad24)") (class "Default")
      (node (ref "U11") (pin "24") (pinfunction "DOUT_24") (pintype "passive+no_connect"))
    )
  )
)
